# matrixkey-adapter.net
KiCad netlist of a schematic drawn in EAGLE
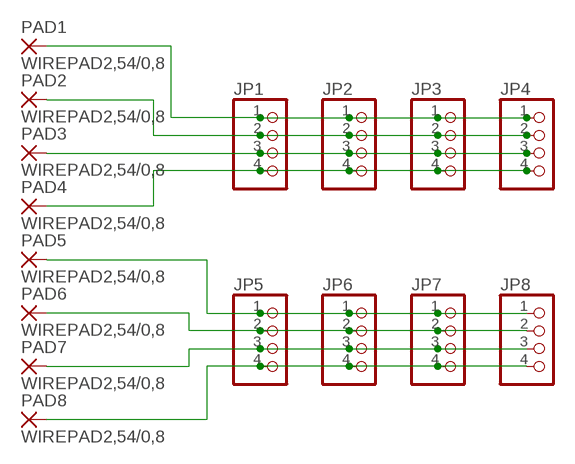
[diagram p0: schematic, sheet 1]

(export (version "E")
  (design (tool "Eeschema 10.0.6"))
  (components
    (comp (ref "JP1")
      (value "PINHD-1X4")
      (footprint "eagle-import:1X04")
      (libsource (lib "eagle-import") (part "PINHD-1X4"))
    )
    (comp (ref "JP2")
      (value "PINHD-1X4")
      (footprint "eagle-import:1X04")
      (libsource (lib "eagle-import") (part "PINHD-1X4"))
    )
    (comp (ref "JP3")
      (value "PINHD-1X4")
      (footprint "eagle-import:1X04")
      (libsource (lib "eagle-import") (part "PINHD-1X4"))
    )
    (comp (ref "JP4")
      (value "PINHD-1X4")
      (footprint "eagle-import:1X04")
      (libsource (lib "eagle-import") (part "PINHD-1X4"))
    )
    (comp (ref "JP5")
      (value "PINHD-1X4")
      (footprint "eagle-import:1X04")
      (libsource (lib "eagle-import") (part "PINHD-1X4"))
    )
    (comp (ref "JP6")
      (value "PINHD-1X4")
      (footprint "eagle-import:1X04")
      (libsource (lib "eagle-import") (part "PINHD-1X4"))
    )
    (comp (ref "JP7")
      (value "PINHD-1X4")
      (footprint "eagle-import:1X04")
      (libsource (lib "eagle-import") (part "PINHD-1X4"))
    )
    (comp (ref "JP8")
      (value "PINHD-1X4")
      (footprint "eagle-import:1X04")
      (libsource (lib "eagle-import") (part "PINHD-1X4"))
    )
    (comp (ref "PAD1")
      (value "WIREPAD2,54/0,8")
      (footprint "eagle-import:2,54_0,8")
      (libsource (lib "eagle-import") (part "WIREPAD2,54/0,8"))
    )
    (comp (ref "PAD2")
      (value "WIREPAD2,54/0,8")
      (footprint "eagle-import:2,54_0,8")
      (libsource (lib "eagle-import") (part "WIREPAD2,54/0,8"))
    )
    (comp (ref "PAD3")
      (value "WIREPAD2,54/0,8")
      (footprint "eagle-import:2,54_0,8")
      (libsource (lib "eagle-import") (part "WIREPAD2,54/0,8"))
    )
    (comp (ref "PAD4")
      (value "WIREPAD2,54/0,8")
      (footprint "eagle-import:2,54_0,8")
      (libsource (lib "eagle-import") (part "WIREPAD2,54/0,8"))
    )
    (comp (ref "PAD5")
      (value "WIREPAD2,54/0,8")
      (footprint "eagle-import:2,54_0,8")
      (libsource (lib "eagle-import") (part "WIREPAD2,54/0,8"))
    )
    (comp (ref "PAD6")
      (value "WIREPAD2,54/0,8")
      (footprint "eagle-import:2,54_0,8")
      (libsource (lib "eagle-import") (part "WIREPAD2,54/0,8"))
    )
    (comp (ref "PAD7")
      (value "WIREPAD2,54/0,8")
      (footprint "eagle-import:2,54_0,8")
      (libsource (lib "eagle-import") (part "WIREPAD2,54/0,8"))
    )
    (comp (ref "PAD8")
      (value "WIREPAD2,54/0,8")
      (footprint "eagle-import:2,54_0,8")
      (libsource (lib "eagle-import") (part "WIREPAD2,54/0,8"))
    )
  )
  (nets
    (net (code "1") (name "Net-(PAD1-P)") (class "Default")
      (node (ref "JP1") (pin "1") (pinfunction "1_1") (pintype "passive"))
      (node (ref "JP2") (pin "1") (pinfunction "1_1") (pintype "passive"))
      (node (ref "JP3") (pin "1") (pinfunction "1_1") (pintype "passive"))
      (node (ref "JP4") (pin "1") (pinfunction "1_1") (pintype "passive"))
      (node (ref "PAD1") (pin "1") (pinfunction "P_1") (pintype "passive"))
    )
    (net (code "2") (name "Net-(PAD2-P)") (class "Default")
      (node (ref "JP1") (pin "2") (pinfunction "2_2") (pintype "passive"))
      (node (ref "JP2") (pin "2") (pinfunction "2_2") (pintype "passive"))
      (node (ref "JP3") (pin "2") (pinfunction "2_2") (pintype "passive"))
      (node (ref "JP4") (pin "2") (pinfunction "2_2") (pintype "passive"))
      (node (ref "PAD2") (pin "1") (pinfunction "P_1") (pintype "passive"))
    )
    (net (code "3") (name "Net-(PAD3-P)") (class "Default")
      (node (ref "JP1") (pin "3") (pinfunction "3_3") (pintype "passive"))
      (node (ref "JP2") (pin "3") (pinfunction "3_3") (pintype "passive"))
      (node (ref "JP3") (pin "3") (pinfunction "3_3") (pintype "passive"))
      (node (ref "JP4") (pin "3") (pinfunction "3_3") (pintype "passive"))
      (node (ref "PAD3") (pin "1") (pinfunction "P_1") (pintype "passive"))
    )
    (net (code "4") (name "Net-(PAD4-P)") (class "Default")
      (node (ref "JP1") (pin "4") (pinfunction "4_4") (pintype "passive"))
      (node (ref "JP2") (pin "4") (pinfunction "4_4") (pintype "passive"))
      (node (ref "JP3") (pin "4") (pinfunction "4_4") (pintype "passive"))
      (node (ref "JP4") (pin "4") (pinfunction "4_4") (pintype "passive"))
      (node (ref "PAD4") (pin "1") (pinfunction "P_1") (pintype "passive"))
    )
    (net (code "5") (name "Net-(PAD5-P)") (class "Default")
      (node (ref "JP5") (pin "1") (pinfunction "1_1") (pintype "passive"))
      (node (ref "JP6") (pin "1") (pinfunction "1_1") (pintype "passive"))
      (node (ref "JP7") (pin "1") (pinfunction "1_1") (pintype "passive"))
      (node (ref "JP8") (pin "1") (pinfunction "1_1") (pintype "passive"))
      (node (ref "PAD5") (pin "1") (pinfunction "P_1") (pintype "passive"))
    )
    (net (code "6") (name "Net-(PAD6-P)") (class "Default")
      (node (ref "JP5") (pin "2") (pinfunction "2_2") (pintype "passive"))
      (node (ref "JP6") (pin "2") (pinfunction "2_2") (pintype "passive"))
      (node (ref "JP7") (pin "2") (pinfunction "2_2") (pintype "passive"))
      (node (ref "JP8") (pin "2") (pinfunction "2_2") (pintype "passive"))
      (node (ref "PAD6") (pin "1") (pinfunction "P_1") (pintype "passive"))
    )
    (net (code "7") (name "Net-(PAD7-P)") (class "Default")
      (node (ref "JP5") (pin "3") (pinfunction "3_3") (pintype "passive"))
      (node (ref "JP6") (pin "3") (pinfunction "3_3") (pintype "passive"))
      (node (ref "JP7") (pin "3") (pinfunction "3_3") (pintype "passive"))
      (node (ref "JP8") (pin "3") (pinfunction "3_3") (pintype "passive"))
      (node (ref "PAD7") (pin "1") (pinfunction "P_1") (pintype "passive"))
    )
    (net (code "8") (name "Net-(PAD8-P)") (class "Default")
      (node (ref "JP5") (pin "4") (pinfunction "4_4") (pintype "passive"))
      (node (ref "JP6") (pin "4") (pinfunction "4_4") (pintype "passive"))
      (node (ref "JP7") (pin "4") (pinfunction "4_4") (pintype "passive"))
      (node (ref "JP8") (pin "4") (pinfunction "4_4") (pintype "passive"))
      (node (ref "PAD8") (pin "1") (pinfunction "P_1") (pintype "passive"))
    )
  )
)
